# LPF_Schematic.net
KiCad netlist of a schematic drawn in EAGLE
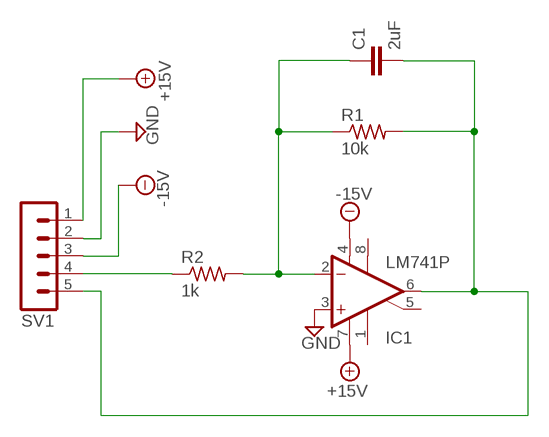
[diagram p0: schematic, sheet 1]

(export (version "E")
  (design (tool "Eeschema 10.0.6"))
  (components
    (comp (ref "C1")
      (value "2uF")
      (footprint "eagle-import:C0603")
      (libsource (lib "eagle-import") (part "C-EUC0603"))
    )
    (comp (ref "IC1")
      (value "LM741P")
      (footprint "eagle-import:DIL08")
      (libsource (lib "eagle-import") (part "741PLM"))
    )
    (comp (ref "R1")
      (value "10k")
      (footprint "eagle-import:R0603")
      (libsource (lib "eagle-import") (part "R-US_R0603"))
    )
    (comp (ref "R2")
      (value "1k")
      (footprint "eagle-import:R0603")
      (libsource (lib "eagle-import") (part "R-US_R0603"))
    )
    (comp (ref "SV1")
      (value "MA05-1")
      (footprint "eagle-import:MA05-1")
      (libsource (lib "eagle-import") (part "MA05-1"))
    )
  )
  (nets
    (net (code "1") (name "+15V") (class "Default")
      (node (ref "IC1") (pin "7") (pinfunction "V+_7") (pintype "power_in"))
      (node (ref "SV1") (pin "1") (pinfunction "1_1") (pintype "passive"))
    )
    (net (code "2") (name "-15V") (class "Default")
      (node (ref "IC1") (pin "4") (pinfunction "V-_4") (pintype "power_in"))
      (node (ref "SV1") (pin "3") (pinfunction "3_3") (pintype "passive"))
    )
    (net (code "3") (name "GND") (class "Default")
      (node (ref "IC1") (pin "3") (pinfunction "+IN_3") (pintype "input"))
      (node (ref "SV1") (pin "2") (pinfunction "2_2") (pintype "passive"))
    )
    (net (code "4") (name "Net-(IC1--IN)") (class "Default")
      (node (ref "C1") (pin "1") (pinfunction "1_1") (pintype "passive"))
      (node (ref "IC1") (pin "2") (pinfunction "-IN_2") (pintype "input"))
      (node (ref "R1") (pin "1") (pinfunction "1_1") (pintype "passive"))
      (node (ref "R2") (pin "2") (pinfunction "2_2") (pintype "passive"))
    )
    (net (code "5") (name "Net-(IC1-OUT)") (class "Default")
      (node (ref "C1") (pin "2") (pinfunction "2_2") (pintype "passive"))
      (node (ref "IC1") (pin "6") (pinfunction "OUT_6") (pintype "output"))
      (node (ref "R1") (pin "2") (pinfunction "2_2") (pintype "passive"))
      (node (ref "SV1") (pin "5") (pinfunction "5_5") (pintype "passive"))
    )
    (net (code "6") (name "Net-(R2-Pad1)") (class "Default")
      (node (ref "R2") (pin "1") (pinfunction "1_1") (pintype "passive"))
      (node (ref "SV1") (pin "4") (pinfunction "4_4") (pintype "passive"))
    )
    (net (code "7") (name "unconnected-(IC1-ON1-Pad1)") (class "Default")
      (node (ref "IC1") (pin "1") (pinfunction "ON1_1") (pintype "passive"))
    )
    (net (code "8") (name "unconnected-(IC1-ON2-Pad5)") (class "Default")
      (node (ref "IC1") (pin "5") (pinfunction "ON2_5") (pintype "passive"))
    )
    (net (code "9") (name "unconnected-(IC1-OPT-Pad8)") (class "Default")
      (node (ref "IC1") (pin "8") (pinfunction "OPT_8") (pintype "passive"))
    )
  )
)
